# PV_MotorIO.net
KiCad netlist of a schematic drawn in Altium Designer
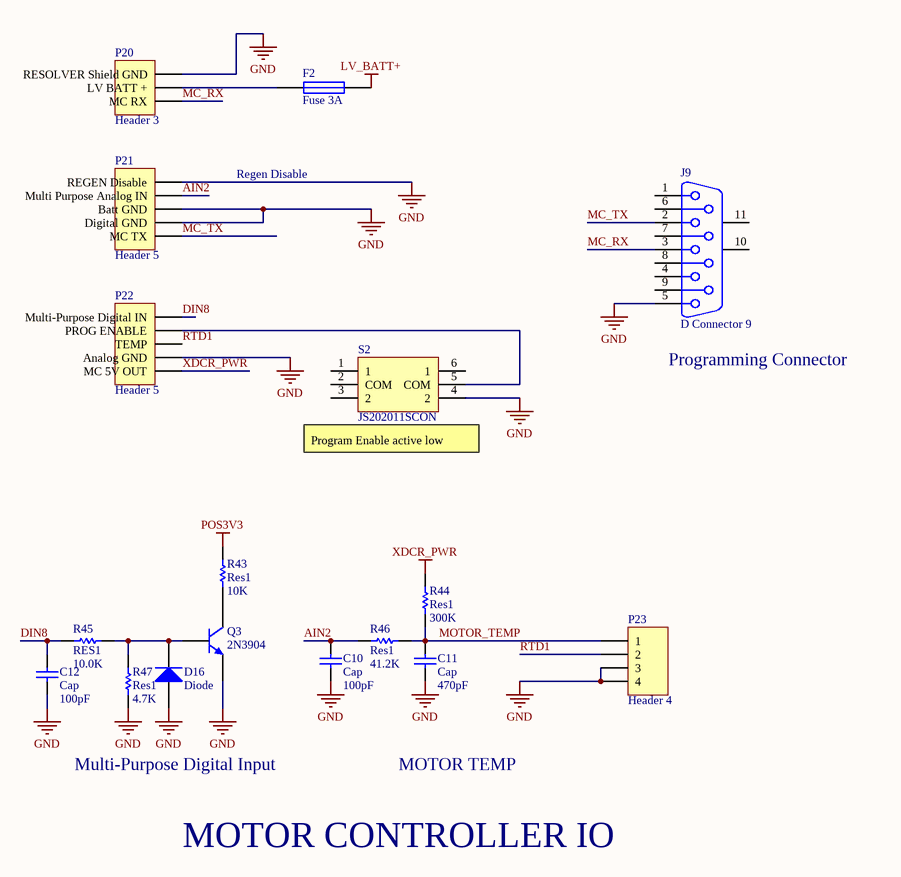
[diagram p0: PV_MotorIO.SchDoc]

(export (version "E")
  (design (tool "Eeschema 10.0.6"))
  (components
    (comp (ref "C10")
      (value "Cap")
      (footprint "1206")
      (description "Capacitor")
      (fields (field (name "ALTIUM_VALUE") "100pF") (field (name "PUBLISHER") "Altium Limited"))
      (libsource (lib "Miscellaneous Devices") (part "Cap"))
    )
    (comp (ref "C11")
      (value "Cap")
      (footprint "1206")
      (description "Capacitor")
      (fields (field (name "ALTIUM_VALUE") "470pF") (field (name "PUBLISHER") "Altium Limited"))
      (libsource (lib "Miscellaneous Devices") (part "Cap"))
    )
    (comp (ref "C12")
      (value "Cap")
      (footprint "1206")
      (description "Capacitor")
      (fields (field (name "ALTIUM_VALUE") "100pF") (field (name "PUBLISHER") "Altium Limited"))
      (libsource (lib "Miscellaneous Devices") (part "Cap"))
    )
    (comp (ref "D16")
      (value "Diode")
      (footprint "1206 DIODE")
      (description "Default Diode")
      (fields (field (name "PUBLISHER") "Altium Limited"))
      (libsource (lib "Miscellaneous Devices") (part "Diode"))
    )
    (comp (ref "F2")
      (value "Fuse 3A")
      (footprint "1A FUSE HOLDER")
      (description "Fuse")
      (fields (field (name "PUBLISHER") "Altium Limited"))
      (libsource (lib "Miscellaneous Devices") (part "Fuse 1"))
    )
    (comp (ref "J9")
      (value "D Connector 9")
      (footprint "DSUB1.385-2H9")
      (description "Receptacle Assembly, 9 Position, Right Angle")
      (fields (field (name "PUBLISHER") "Altium Limited"))
      (libsource (lib "Miscellaneous Connectors") (part "D Connector 9"))
    )
    (comp (ref "P20")
      (value "Header 3")
      (footprint "3POS TERM BLOCK")
      (description "Header, 3-Pin")
      (fields (field (name "PUBLISHER") "Altium Limited"))
      (libsource (lib "Miscellaneous Connectors") (part "Header 3"))
    )
    (comp (ref "P21")
      (value "Header 5")
      (footprint "5POS TERM BLOCK")
      (description "Header, 5-Pin")
      (fields (field (name "PUBLISHER") "Altium Limited"))
      (libsource (lib "Miscellaneous Connectors") (part "Header 5"))
    )
    (comp (ref "P22")
      (value "Header 5")
      (footprint "5POS TERM BLOCK")
      (description "Header, 5-Pin")
      (fields (field (name "PUBLISHER") "Altium Limited"))
      (libsource (lib "Miscellaneous Connectors") (part "Header 5"))
    )
    (comp (ref "P23")
      (value "Header 4")
      (footprint "4POS TERM BLOCK")
      (description "Header, 4-Pin")
      (fields (field (name "PUBLISHER") "Altium Limited"))
      (libsource (lib "Miscellaneous Connectors") (part "Header 4"))
    )
    (comp (ref "Q3")
      (value "2N3904")
      (footprint "BJT")
      (description "NPN General Purpose Amplifier")
      (fields (field (name "PUBLISHER") "Altium Limited"))
      (libsource (lib "Miscellaneous Devices") (part "2N3904"))
    )
    (comp (ref "R43")
      (value "Res1")
      (footprint "1206")
      (description "Resistor")
      (fields (field (name "ALTIUM_VALUE") "10K") (field (name "PUBLISHER") "Altium Limited"))
      (libsource (lib "Miscellaneous Devices") (part "Res1"))
    )
    (comp (ref "R44")
      (value "Res1")
      (footprint "1206")
      (description "Resistor")
      (fields (field (name "ALTIUM_VALUE") "300K") (field (name "PUBLISHER") "Altium Limited"))
      (libsource (lib "Miscellaneous Devices") (part "Res1"))
    )
    (comp (ref "R45")
      (value "RES1")
      (footprint "1206")
      (description "Resistor")
      (fields (field (name "ALTIUM_VALUE") "10.0K") (field (name "PUBLISHER") "Altium Limited"))
      (libsource (lib "Miscellaneous Devices") (part "Res1"))
    )
    (comp (ref "R46")
      (value "Res1")
      (footprint "1206")
      (description "Resistor")
      (fields (field (name "ALTIUM_VALUE") "41.2K") (field (name "PUBLISHER") "Altium Limited"))
      (libsource (lib "Miscellaneous Devices") (part "Res1"))
    )
    (comp (ref "R47")
      (value "Res1")
      (footprint "1206")
      (description "Resistor")
      (fields (field (name "ALTIUM_VALUE") "4.7K") (field (name "PUBLISHER") "Altium Limited"))
      (libsource (lib "Miscellaneous Devices") (part "Res1"))
    )
    (comp (ref "S2")
      (value "JS202011SCON")
      (footprint "JS202011SCON")
      (description "DPST Switch")
      (libsource (lib "ic") (part "JS202011SCON"))
    )
  )
  (nets
    (net (code "1") (name "/AIN2") (class "Default")
      (node (ref "C10") (pin "2") (pinfunction "2_2") (pintype "passive"))
      (node (ref "P21") (pin "4") (pinfunction "PROG_ENABLE_4") (pintype "passive"))
      (node (ref "R46") (pin "2") (pinfunction "2_2") (pintype "passive"))
    )
    (net (code "2") (name "/DIN8") (class "Default")
      (node (ref "C12") (pin "2") (pinfunction "2_2") (pintype "passive"))
      (node (ref "P22") (pin "5") (pinfunction "Multi-Purpose_Digital_IN_5") (pintype "passive"))
      (node (ref "R45") (pin "1") (pinfunction "1_1") (pintype "passive"))
    )
    (net (code "3") (name "/MC_RX") (class "Default")
      (node (ref "J9") (pin "3") (pinfunction "3_3") (pintype "passive"))
      (node (ref "P20") (pin "1") (pinfunction "MC_RX_1") (pintype "passive"))
    )
    (net (code "4") (name "/MC_TX") (class "Default")
      (node (ref "J9") (pin "2") (pinfunction "2_2") (pintype "passive"))
      (node (ref "P21") (pin "1") (pinfunction "MC_5V_OUT_1") (pintype "passive"))
    )
    (net (code "5") (name "/MOTOR_TEMP") (class "Default")
      (node (ref "C11") (pin "2") (pinfunction "2_2") (pintype "passive"))
      (node (ref "P23") (pin "1") (pinfunction "1_1") (pintype "passive"))
      (node (ref "R44") (pin "1") (pinfunction "1_1") (pintype "passive"))
      (node (ref "R46") (pin "1") (pinfunction "1_1") (pintype "passive"))
    )
    (net (code "6") (name "/RTD1") (class "Default")
      (node (ref "P22") (pin "3") (pinfunction "TEMP_3") (pintype "passive"))
      (node (ref "P23") (pin "2") (pinfunction "2_2") (pintype "passive"))
    )
    (net (code "7") (name "GND") (class "Default")
      (node (ref "C10") (pin "1") (pinfunction "1_1") (pintype "passive"))
      (node (ref "C11") (pin "1") (pinfunction "1_1") (pintype "passive"))
      (node (ref "C12") (pin "1") (pinfunction "1_1") (pintype "passive"))
      (node (ref "D16") (pin "1") (pinfunction "A_1") (pintype "passive"))
      (node (ref "J9") (pin "5") (pinfunction "5_5") (pintype "passive"))
      (node (ref "P20") (pin "3") (pinfunction "RESOLVER_Shield_GND_3") (pintype "passive"))
      (node (ref "P21") (pin "2") (pinfunction "Analog_GND_2") (pintype "passive"))
      (node (ref "P21") (pin "3") (pinfunction "TEMP_3") (pintype "passive"))
      (node (ref "P21") (pin "5") (pinfunction "Multi-Purpose_Digital_IN_5") (pintype "passive"))
      (node (ref "P22") (pin "2") (pinfunction "Analog_GND_2") (pintype "passive"))
      (node (ref "P23") (pin "3") (pinfunction "3_3") (pintype "passive"))
      (node (ref "P23") (pin "4") (pinfunction "4_4") (pintype "passive"))
      (node (ref "Q3") (pin "1") (pinfunction "E_1") (pintype "passive"))
      (node (ref "R47") (pin "1") (pinfunction "1_1") (pintype "passive"))
      (node (ref "S2") (pin "4") (pinfunction "2_4") (pintype "passive"))
    )
    (net (code "8") (name "LV_BATT+") (class "Default")
      (node (ref "F2") (pin "2") (pinfunction "2_2") (pintype "passive"))
    )
    (net (code "9") (name "Net-(D16-K)") (class "Default")
      (node (ref "D16") (pin "2") (pinfunction "K_2") (pintype "passive"))
      (node (ref "Q3") (pin "2") (pinfunction "B_2") (pintype "passive"))
      (node (ref "R45") (pin "2") (pinfunction "2_2") (pintype "passive"))
      (node (ref "R47") (pin "2") (pinfunction "2_2") (pintype "passive"))
    )
    (net (code "10") (name "Net-(P20-LV_BATT_+)") (class "Default")
      (node (ref "F2") (pin "1") (pinfunction "1_1") (pintype "passive"))
      (node (ref "P20") (pin "2") (pinfunction "LV_BATT_+_2") (pintype "passive"))
    )
    (net (code "11") (name "Net-(P22-PROG_ENABLE)") (class "Default")
      (node (ref "P22") (pin "4") (pinfunction "PROG_ENABLE_4") (pintype "passive"))
      (node (ref "S2") (pin "5") (pinfunction "COM_5") (pintype "passive"))
    )
    (net (code "12") (name "Net-(Q3-C)") (class "Default")
      (node (ref "Q3") (pin "3") (pinfunction "C_3") (pintype "passive"))
      (node (ref "R43") (pin "1") (pinfunction "1_1") (pintype "passive"))
    )
    (net (code "13") (name "POS3V3") (class "Default")
      (node (ref "R43") (pin "2") (pinfunction "2_2") (pintype "passive"))
    )
    (net (code "14") (name "XDCR_PWR") (class "Default")
      (node (ref "P22") (pin "1") (pinfunction "MC_5V_OUT_1") (pintype "passive"))
      (node (ref "R44") (pin "2") (pinfunction "2_2") (pintype "passive"))
    )
    (net (code "15") (name "unconnected-(J9-MH1-Pad10)") (class "Default")
      (node (ref "J9") (pin "10") (pinfunction "MH1_10") (pintype "passive"))
    )
    (net (code "16") (name "unconnected-(J9-MH2-Pad11)") (class "Default")
      (node (ref "J9") (pin "11") (pinfunction "MH2_11") (pintype "passive"))
    )
    (net (code "17") (name "unconnected-(J9-Pad1)") (class "Default")
      (node (ref "J9") (pin "1") (pinfunction "1_1") (pintype "passive"))
    )
    (net (code "18") (name "unconnected-(J9-Pad4)") (class "Default")
      (node (ref "J9") (pin "4") (pinfunction "4_4") (pintype "passive"))
    )
    (net (code "19") (name "unconnected-(J9-Pad6)") (class "Default")
      (node (ref "J9") (pin "6") (pinfunction "6_6") (pintype "passive"))
    )
    (net (code "20") (name "unconnected-(J9-Pad7)") (class "Default")
      (node (ref "J9") (pin "7") (pinfunction "7_7") (pintype "passive"))
    )
    (net (code "21") (name "unconnected-(J9-Pad8)") (class "Default")
      (node (ref "J9") (pin "8") (pinfunction "8_8") (pintype "passive"))
    )
    (net (code "22") (name "unconnected-(J9-Pad9)") (class "Default")
      (node (ref "J9") (pin "9") (pinfunction "9_9") (pintype "passive"))
    )
    (net (code "23") (name "unconnected-(S2-1-Pad6)") (class "Default")
      (node (ref "S2") (pin "6") (pinfunction "1_6") (pintype "passive"))
    )
    (net (code "24") (name "unconnected-(S2-2-Pad3)") (class "Default")
      (node (ref "S2") (pin "3") (pinfunction "2_3") (pintype "passive"))
    )
    (net (code "25") (name "unconnected-(S2-COM-Pad2)") (class "Default")
      (node (ref "S2") (pin "2") (pinfunction "COM_2") (pintype "passive"))
    )
    (net (code "26") (name "unconnected-(S2-Pad1)") (class "Default")
      (node (ref "S2") (pin "1") (pinfunction "1_1") (pintype "passive"))
    )
  )
)
